# 3V3_Isolation.net
KiCad netlist of a schematic drawn in Altium Designer
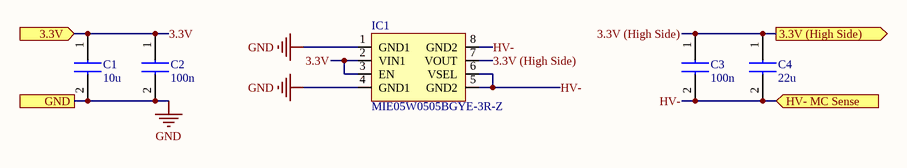
[diagram p0: 3V3_Isolation.SchDoc]

(export (version "E")
  (design (tool "Eeschema 10.0.6"))
  (components
    (comp (ref "C1")
      (value "10u")
      (footprint "SamacSys:CAPC1608X90N")
      (description "Capacitor")
      (fields (field (name "MANUFACTURER_PART_NUMBER") "CL10A106KQ8NNNL"))
      (libsource (lib "*") (part "CL10A106KQ8NNNL"))
    )
    (comp (ref "C2")
      (value "100n")
      (footprint "SamacSys:CAPC1608X90N")
      (description "Capacitor")
      (fields
        (field (name "MANUFACTURER_PART_NUMBER") "06035C104J4Z2A")
        (field (name "MOUSER PART NUMBER") "581-06035C104J4Z2A")
      )
      (libsource (lib "*") (part "06035C104J4Z2A"))
    )
    (comp (ref "C3")
      (value "100n")
      (footprint "SamacSys:CAPC1608X90N")
      (description "Capacitor")
      (fields
        (field (name "MANUFACTURER_PART_NUMBER") "06035C104J4Z2A")
        (field (name "MOUSER PART NUMBER") "581-06035C104J4Z2A")
      )
      (libsource (lib "*") (part "06035C104J4Z2A"))
    )
    (comp (ref "C4")
      (value "22u")
      (footprint "SamacSys:CAPC1608X105N")
      (description "Capacitor")
      (fields
        (field (name "MANUFACTURER_PART_NUMBER") "CL10A226MP8NUNE")
        (field (name "MOUSER PART NUMBER") "187-CL10A226MP8NUNE")
      )
      (libsource (lib "*") (part "CL10A226MP8NUNE"))
    )
    (comp (ref "IC1")
      (value "MIE05W0505BGYE-3R-Z")
      (footprint "SOIC127P1030X265-8N")
      (libsource (lib "SamacSys") (part "MIE05W0505BGYE-3R-Z"))
    )
  )
  (nets
    (net (code "1") (name "/3.3V") (class "Default")
      (node (ref "C1") (pin "1") (pinfunction "1_1") (pintype "passive"))
      (node (ref "C2") (pin "1") (pinfunction "1_1") (pintype "passive"))
      (node (ref "IC1") (pin "2") (pinfunction "VIN1_2") (pintype "passive"))
      (node (ref "IC1") (pin "3") (pinfunction "EN_3") (pintype "passive"))
    )
    (net (code "2") (name "/3.3V (High Side)") (class "Default")
      (node (ref "C3") (pin "1") (pinfunction "1_1") (pintype "passive"))
      (node (ref "C4") (pin "1") (pinfunction "1_1") (pintype "passive"))
      (node (ref "IC1") (pin "7") (pinfunction "VOUT_7") (pintype "passive"))
    )
    (net (code "3") (name "/HV-") (class "Default")
      (node (ref "C3") (pin "2") (pinfunction "2_2") (pintype "passive"))
      (node (ref "C4") (pin "2") (pinfunction "2_2") (pintype "passive"))
      (node (ref "IC1") (pin "5") (pinfunction "GND2_5") (pintype "passive"))
      (node (ref "IC1") (pin "6") (pinfunction "VSEL_6") (pintype "passive"))
      (node (ref "IC1") (pin "8") (pinfunction "GND2_8") (pintype "passive"))
    )
    (net (code "4") (name "GND") (class "Default")
      (node (ref "C1") (pin "2") (pinfunction "2_2") (pintype "passive"))
      (node (ref "C2") (pin "2") (pinfunction "2_2") (pintype "passive"))
      (node (ref "IC1") (pin "1") (pinfunction "GND1_1") (pintype "passive"))
      (node (ref "IC1") (pin "4") (pinfunction "GND1_4") (pintype "passive"))
    )
  )
)
